# Current_Controller.net
KiCad netlist of a schematic drawn in EAGLE
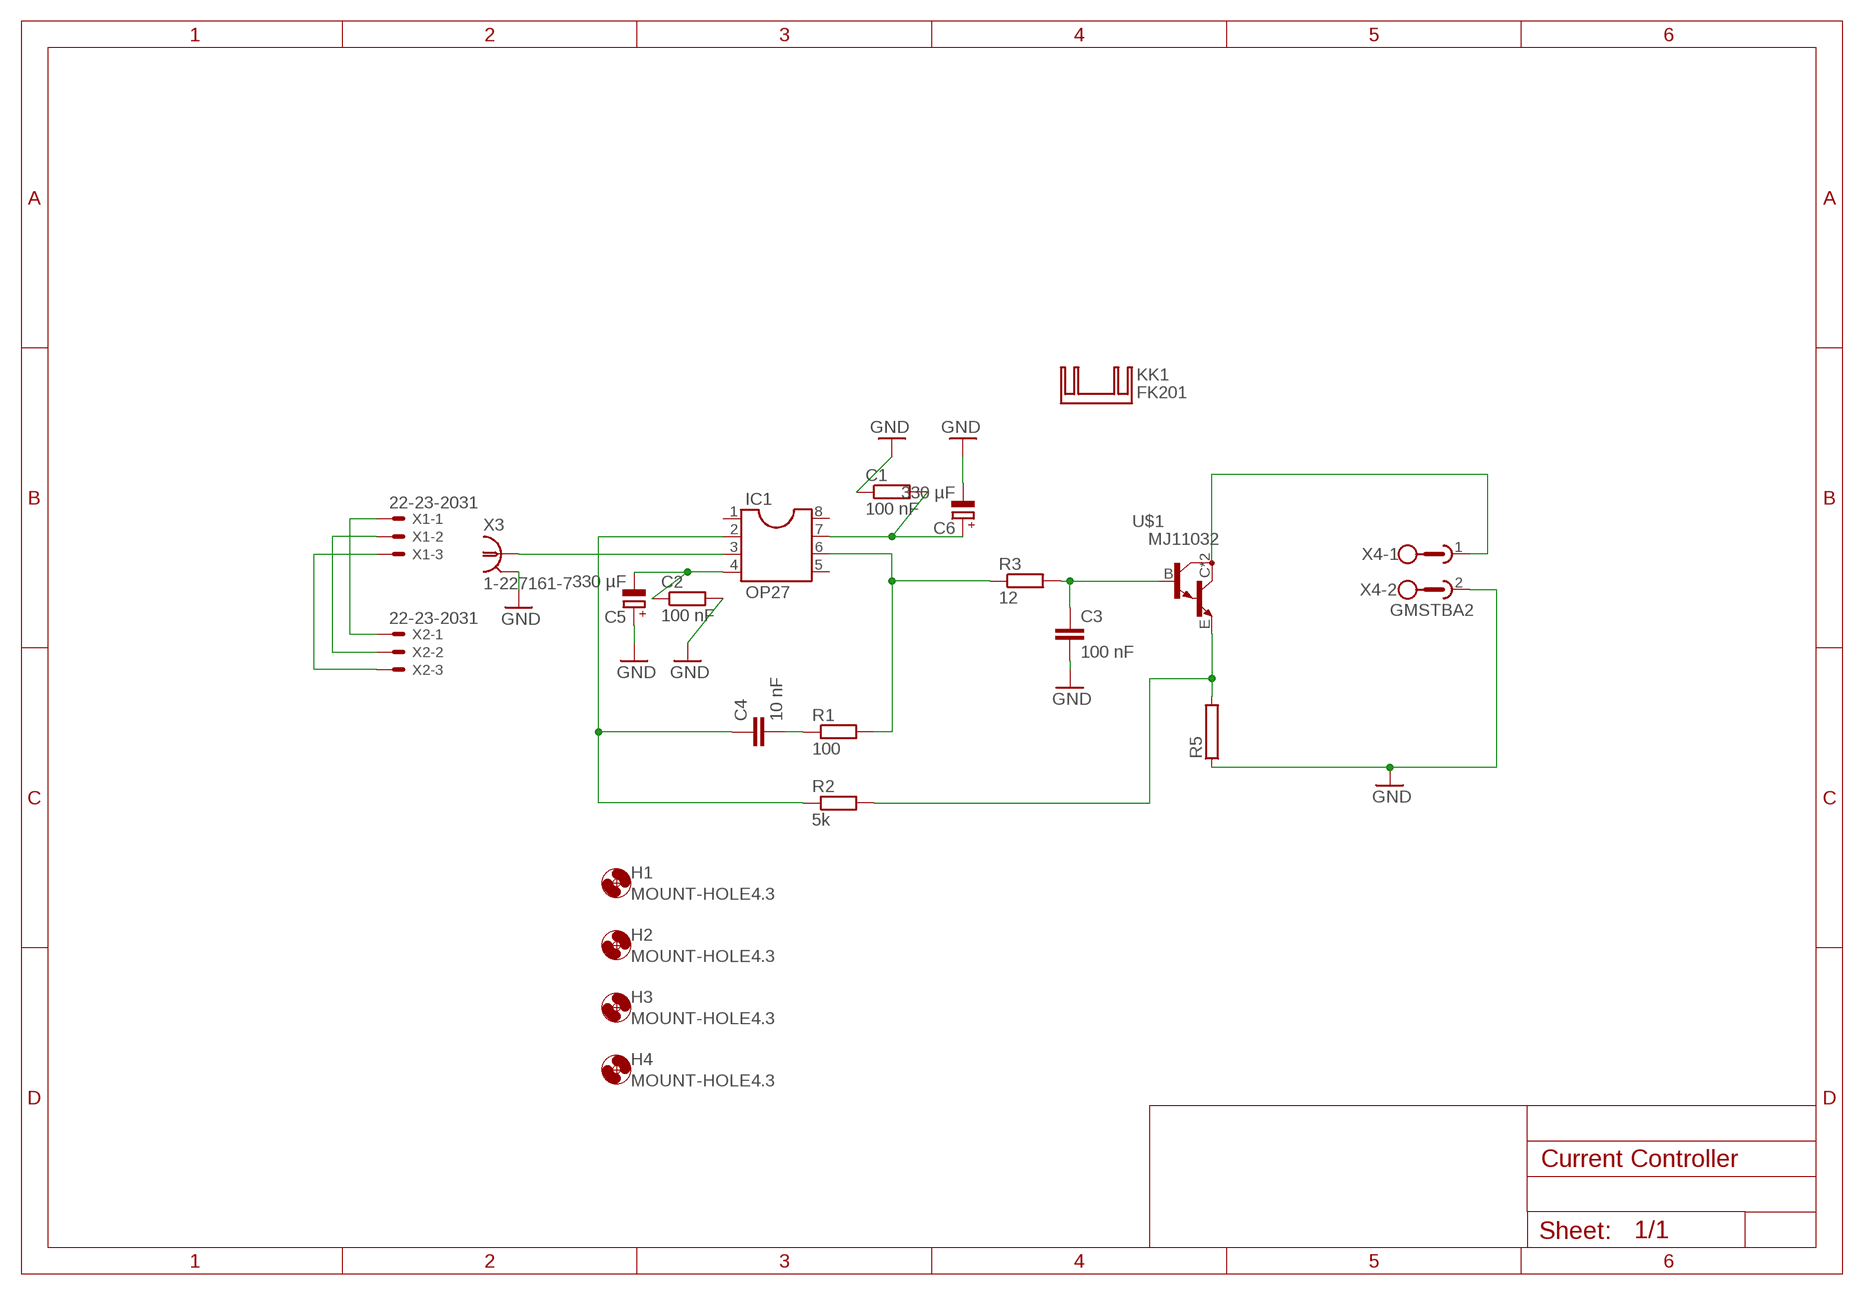
[diagram p0: schematic, sheet 1]

(export (version "E")
  (design (tool "Eeschema 10.0.6"))
  (components
    (comp (ref "C1")
      (value "100 nF")
      (footprint "eagle-import:M1206")
      (libsource (lib "eagle-import") (part "R-EU_M1206"))
    )
    (comp (ref "C2")
      (value "100 nF")
      (footprint "eagle-import:M1206")
      (libsource (lib "eagle-import") (part "R-EU_M1206"))
    )
    (comp (ref "C3")
      (value "100 nF")
      (footprint "eagle-import:C025-050X050")
      (libsource (lib "eagle-import") (part "C-EU025-050X050"))
    )
    (comp (ref "C4")
      (value "10 nF")
      (footprint "eagle-import:C025-050X050")
      (libsource (lib "eagle-import") (part "C-EU025-050X050"))
    )
    (comp (ref "C5")
      (value "330 µF")
      (footprint "eagle-import:E5-8,5")
      (libsource (lib "eagle-import") (part "CPOL-EUE5-8.5"))
    )
    (comp (ref "C6")
      (value "330 µF")
      (footprint "eagle-import:E5-8,5")
      (libsource (lib "eagle-import") (part "CPOL-EUE5-8.5"))
    )
    (comp (ref "H1")
      (value "MOUNT-HOLE4.3")
      (footprint "eagle-import:4,3")
      (libsource (lib "eagle-import") (part "MOUNT-HOLE4.3"))
    )
    (comp (ref "H2")
      (value "MOUNT-HOLE4.3")
      (footprint "eagle-import:4,3")
      (libsource (lib "eagle-import") (part "MOUNT-HOLE4.3"))
    )
    (comp (ref "H3")
      (value "MOUNT-HOLE4.3")
      (footprint "eagle-import:4,3")
      (libsource (lib "eagle-import") (part "MOUNT-HOLE4.3"))
    )
    (comp (ref "H4")
      (value "MOUNT-HOLE4.3")
      (footprint "eagle-import:4,3")
      (libsource (lib "eagle-import") (part "MOUNT-HOLE4.3"))
    )
    (comp (ref "IC1")
      (value "OP27")
      (footprint "eagle-import:DIL08")
      (libsource (lib "eagle-import") (part "DIL8"))
    )
    (comp (ref "KK1")
      (value "FK201")
      (footprint "eagle-import:FK201")
      (libsource (lib "eagle-import") (part "FK201"))
    )
    (comp (ref "R1")
      (value "100")
      (footprint "eagle-import:0309_12")
      (libsource (lib "eagle-import") (part "resistor_348_R-EU_0309/12"))
    )
    (comp (ref "R2")
      (value "5k")
      (footprint "eagle-import:0309_12")
      (libsource (lib "eagle-import") (part "resistor_348_R-EU_0309/12"))
    )
    (comp (ref "R3")
      (value "12")
      (footprint "eagle-import:0309_12")
      (libsource (lib "eagle-import") (part "resistor_348_R-EU_0309/12"))
    )
    (comp (ref "R5")
      (value "RRWM10X64")
      (footprint "eagle-import:RWM10X64")
      (libsource (lib "eagle-import") (part "RRWM10X64"))
    )
    (comp (ref "U$1")
      (value "MJ11032")
      (footprint "eagle-import:TO3_")
      (libsource (lib "eagle-import") (part "MJ11032"))
    )
    (comp (ref "X1")
      (value "22-23-2031")
      (footprint "eagle-import:22-23-2031")
      (fields (field (name "MF") "MOLEX"))
      (libsource (lib "eagle-import") (part "22-23-2031"))
    )
    (comp (ref "X2")
      (value "22-23-2031")
      (footprint "eagle-import:22-23-2031")
      (fields (field (name "MF") "MOLEX"))
      (libsource (lib "eagle-import") (part "22-23-2031"))
    )
    (comp (ref "X3")
      (value "1-227161-7")
      (footprint "eagle-import:AMP_227161")
      (fields (field (name "MF") "TYCO ELECTRONICS"))
      (libsource (lib "eagle-import") (part "?2271611--7"))
    )
    (comp (ref "X4")
      (value "GMSTBA2")
      (footprint "eagle-import:GMSTBA2")
      (fields (field (name "MF") "FARNELL") (field (name "MPN") "1757242"))
      (libsource (lib "eagle-import") (part "GMSTBA2"))
    )
  )
  (nets
    (net (code "1") (name "/V+") (class "Default")
      (node (ref "C1") (pin "2") (pinfunction "2_2") (pintype "passive"))
      (node (ref "C6") (pin "+") (pinfunction "+_+") (pintype "passive"))
      (node (ref "IC1") (pin "7") (pinfunction "7_7") (pintype "passive"))
      (node (ref "X1") (pin "1") (pinfunction "S_1") (pintype "passive"))
      (node (ref "X2") (pin "1") (pinfunction "S_1") (pintype "passive"))
    )
    (net (code "2") (name "/V-") (class "Default")
      (node (ref "C2") (pin "1") (pinfunction "1_1") (pintype "passive"))
      (node (ref "C5") (pin "-") (pinfunction "-_-") (pintype "passive"))
      (node (ref "IC1") (pin "4") (pinfunction "4_4") (pintype "passive"))
      (node (ref "X1") (pin "3") (pinfunction "S_3") (pintype "passive"))
      (node (ref "X2") (pin "3") (pinfunction "S_3") (pintype "passive"))
    )
    (net (code "3") (name "GND") (class "Default")
      (node (ref "C1") (pin "1") (pinfunction "1_1") (pintype "passive"))
      (node (ref "C2") (pin "2") (pinfunction "2_2") (pintype "passive"))
      (node (ref "C3") (pin "2") (pinfunction "2_2") (pintype "passive"))
      (node (ref "C5") (pin "+") (pinfunction "+_+") (pintype "passive"))
      (node (ref "C6") (pin "-") (pinfunction "-_-") (pintype "passive"))
      (node (ref "R5") (pin "1") (pinfunction "1_1") (pintype "passive"))
      (node (ref "X1") (pin "2") (pinfunction "S_2") (pintype "passive"))
      (node (ref "X2") (pin "2") (pinfunction "S_2") (pintype "passive"))
      (node (ref "X3") (pin "2") (pinfunction "2_2") (pintype "passive"))
      (node (ref "X4") (pin "2") (pinfunction "1_2") (pintype "passive"))
    )
    (net (code "4") (name "Net-(C3-Pad1)") (class "Default")
      (node (ref "C3") (pin "1") (pinfunction "1_1") (pintype "passive"))
      (node (ref "R3") (pin "2") (pinfunction "2_2") (pintype "passive"))
      (node (ref "U$1") (pin "B") (pinfunction "B_B") (pintype "passive"))
    )
    (net (code "5") (name "Net-(C4-Pad1)") (class "Default")
      (node (ref "C4") (pin "1") (pinfunction "1_1") (pintype "passive"))
      (node (ref "IC1") (pin "2") (pinfunction "2_2") (pintype "passive"))
      (node (ref "R2") (pin "1") (pinfunction "1_1") (pintype "passive"))
    )
    (net (code "6") (name "Net-(C4-Pad2)") (class "Default")
      (node (ref "C4") (pin "2") (pinfunction "2_2") (pintype "passive"))
      (node (ref "R1") (pin "1") (pinfunction "1_1") (pintype "passive"))
    )
    (net (code "7") (name "Net-(IC1-Pad3)") (class "Default")
      (node (ref "IC1") (pin "3") (pinfunction "3_3") (pintype "passive"))
      (node (ref "X3") (pin "1") (pinfunction "1_1") (pintype "passive"))
    )
    (net (code "8") (name "Net-(IC1-Pad6)") (class "Default")
      (node (ref "IC1") (pin "6") (pinfunction "6_6") (pintype "passive"))
      (node (ref "R1") (pin "2") (pinfunction "2_2") (pintype "passive"))
      (node (ref "R3") (pin "1") (pinfunction "1_1") (pintype "passive"))
    )
    (net (code "9") (name "Net-(R2-Pad2)") (class "Default")
      (node (ref "R2") (pin "2") (pinfunction "2_2") (pintype "passive"))
      (node (ref "R5") (pin "2") (pinfunction "2_2") (pintype "passive"))
      (node (ref "U$1") (pin "E") (pinfunction "E_E") (pintype "passive"))
    )
    (net (code "10") (name "Net-(U$1-C-PadC{slash})") (class "Default")
      (node (ref "U$1") (pin "C") (pinfunction "C_C") (pintype "passive"))
      (node (ref "U$1") (pin "C/") (pinfunction "C_C/") (pintype "passive"))
      (node (ref "X4") (pin "1") (pinfunction "1_1") (pintype "passive"))
    )
    (net (code "11") (name "unconnected-(IC1-Pad1)") (class "Default")
      (node (ref "IC1") (pin "1") (pinfunction "1_1") (pintype "passive"))
    )
    (net (code "12") (name "unconnected-(IC1-Pad5)") (class "Default")
      (node (ref "IC1") (pin "5") (pinfunction "5_5") (pintype "passive"))
    )
    (net (code "13") (name "unconnected-(IC1-Pad8)") (class "Default")
      (node (ref "IC1") (pin "8") (pinfunction "8_8") (pintype "passive"))
    )
  )
)
